# V2_aktuell_StdTeile.net
KiCad netlist of a schematic drawn in EAGLE
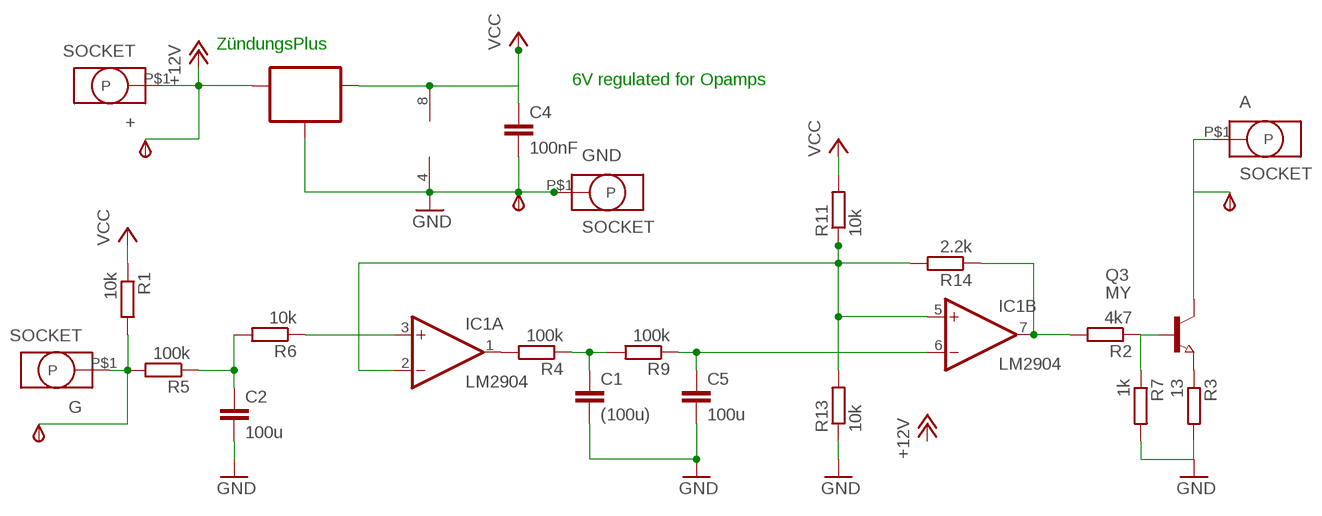
[diagram p0: schematic, sheet 1]

(export (version "E")
  (design (tool "Eeschema 10.0.6"))
  (components
    (comp (ref "+")
      (value "SOCKET")
      (footprint "eagle-import:ID2.5MM")
      (libsource (lib "eagle-import") (part "SOCKET"))
    )
    (comp (ref "A")
      (value "SOCKET")
      (footprint "eagle-import:ID2.5MM")
      (libsource (lib "eagle-import") (part "SOCKET"))
    )
    (comp (ref "C1")
      (value "(100u)")
      (footprint "eagle-import:C1206K")
      (libsource (lib "eagle-import") (part "C-EUC1206K"))
    )
    (comp (ref "C2")
      (value "100u")
      (footprint "eagle-import:C1206K")
      (libsource (lib "eagle-import") (part "C-EUC1206K"))
    )
    (comp (ref "C4")
      (value "100nF")
      (footprint "eagle-import:C0805")
      (libsource (lib "eagle-import") (part "C-EUC0805"))
    )
    (comp (ref "C5")
      (value "100u")
      (footprint "eagle-import:C1206K")
      (libsource (lib "eagle-import") (part "C-EUC1206K"))
    )
    (comp (ref "G")
      (value "SOCKET")
      (footprint "eagle-import:ID2.5MM")
      (libsource (lib "eagle-import") (part "SOCKET"))
    )
    (comp (ref "GND")
      (value "SOCKET")
      (footprint "eagle-import:ID2.5MM")
      (libsource (lib "eagle-import") (part "SOCKET"))
    )
    (comp (ref "GND_")
      (value "TPSB2.0")
      (footprint "eagle-import:B2.0")
      (libsource (lib "eagle-import") (part "TPSB2.0"))
    )
    (comp (ref "IC1")
      (value "LM2904")
      (footprint "eagle-import:SO08")
      (libsource (lib "eagle-import") (part "LM358D"))
    )
    (comp (ref "IC2")
      (value "70L06")
      (footprint "eagle-import:SOT89_ROUND")
      (libsource (lib "eagle-import") (part "78LXXSOT89_ROUND"))
    )
    (comp (ref "IN")
      (value "TPSB2.0")
      (footprint "eagle-import:B2.0")
      (libsource (lib "eagle-import") (part "TPSB2.0"))
    )
    (comp (ref "OUT")
      (value "TPSB2.0")
      (footprint "eagle-import:B2.0")
      (libsource (lib "eagle-import") (part "TPSB2.0"))
    )
    (comp (ref "Q3")
      (value "MY")
      (footprint "eagle-import:SOT89")
      (libsource (lib "eagle-import") (part "NPN-TRANSISTOR_SOT89"))
    )
    (comp (ref "R1")
      (value "10k")
      (footprint "eagle-import:R0805")
      (libsource (lib "eagle-import") (part "R-EU_R0805"))
    )
    (comp (ref "R2")
      (value "4k7")
      (footprint "eagle-import:R0805")
      (libsource (lib "eagle-import") (part "R-EU_R0805"))
    )
    (comp (ref "R3")
      (value "13")
      (footprint "eagle-import:R1206")
      (libsource (lib "eagle-import") (part "R-EU_R1206"))
    )
    (comp (ref "R4")
      (value "100k")
      (footprint "eagle-import:R0805")
      (libsource (lib "eagle-import") (part "R-EU_R0805"))
    )
    (comp (ref "R5")
      (value "100k")
      (footprint "eagle-import:R0805")
      (libsource (lib "eagle-import") (part "R-EU_R0805"))
    )
    (comp (ref "R6")
      (value "10k")
      (footprint "eagle-import:R0805")
      (libsource (lib "eagle-import") (part "R-EU_R0805"))
    )
    (comp (ref "R7")
      (value "1k")
      (footprint "eagle-import:R0805")
      (libsource (lib "eagle-import") (part "R-EU_R0805"))
    )
    (comp (ref "R9")
      (value "100k")
      (footprint "eagle-import:R0805")
      (libsource (lib "eagle-import") (part "R-EU_R0805"))
    )
    (comp (ref "R11")
      (value "10k")
      (footprint "eagle-import:R0805")
      (libsource (lib "eagle-import") (part "R-EU_R0805"))
    )
    (comp (ref "R13")
      (value "10k")
      (footprint "eagle-import:R0805")
      (libsource (lib "eagle-import") (part "R-EU_R0805"))
    )
    (comp (ref "R14")
      (value "2.2k")
      (footprint "eagle-import:R0805")
      (libsource (lib "eagle-import") (part "R-EU_R0805"))
    )
    (comp (ref "V+")
      (value "TPSB2.0")
      (footprint "eagle-import:B2.0")
      (libsource (lib "eagle-import") (part "TPSB2.0"))
    )
  )
  (nets
    (net (code "1") (name "+12V") (class "Default")
      (node (ref "+") (pin "P$1") (pinfunction "P_P$1") (pintype "bidirectional"))
      (node (ref "IC2") (pin "3") (pinfunction "IN_3") (pintype "input"))
      (node (ref "V+") (pin "TP") (pinfunction "PP_TP") (pintype "input"))
    )
    (net (code "2") (name "GND") (class "Default")
      (node (ref "C1") (pin "2") (pinfunction "2_2") (pintype "passive"))
      (node (ref "C2") (pin "2") (pinfunction "2_2") (pintype "passive"))
      (node (ref "C4") (pin "2") (pinfunction "2_2") (pintype "passive"))
      (node (ref "C5") (pin "2") (pinfunction "2_2") (pintype "passive"))
      (node (ref "GND") (pin "P$1") (pinfunction "P_P$1") (pintype "bidirectional"))
      (node (ref "GND_") (pin "TP") (pinfunction "PP_TP") (pintype "input"))
      (node (ref "IC1") (pin "4") (pinfunction "V-_4") (pintype "power_in"))
      (node (ref "IC2") (pin "2") (pinfunction "GND_2") (pintype "input"))
      (node (ref "IC2") (pin "2@1") (pinfunction "GND_2@1") (pintype "input"))
      (node (ref "R13") (pin "1") (pinfunction "1_1") (pintype "passive"))
      (node (ref "R3") (pin "2") (pinfunction "2_2") (pintype "passive"))
      (node (ref "R7") (pin "2") (pinfunction "2_2") (pintype "passive"))
    )
    (net (code "3") (name "Net-(A-P)") (class "Default")
      (node (ref "A") (pin "P$1") (pinfunction "P_P$1") (pintype "bidirectional"))
      (node (ref "OUT") (pin "TP") (pinfunction "PP_TP") (pintype "input"))
      (node (ref "Q3") (pin "2") (pinfunction "C_2") (pintype "passive"))
    )
    (net (code "4") (name "Net-(C1-Pad1)") (class "Default")
      (node (ref "C1") (pin "1") (pinfunction "1_1") (pintype "passive"))
      (node (ref "R4") (pin "1") (pinfunction "1_1") (pintype "passive"))
      (node (ref "R9") (pin "2") (pinfunction "2_2") (pintype "passive"))
    )
    (net (code "5") (name "Net-(C2-Pad1)") (class "Default")
      (node (ref "C2") (pin "1") (pinfunction "1_1") (pintype "passive"))
      (node (ref "R5") (pin "1") (pinfunction "1_1") (pintype "passive"))
      (node (ref "R6") (pin "2") (pinfunction "2_2") (pintype "passive"))
    )
    (net (code "6") (name "Net-(G-P)") (class "Default")
      (node (ref "G") (pin "P$1") (pinfunction "P_P$1") (pintype "bidirectional"))
      (node (ref "IN") (pin "TP") (pinfunction "PP_TP") (pintype "input"))
      (node (ref "R1") (pin "2") (pinfunction "2_2") (pintype "passive"))
      (node (ref "R5") (pin "2") (pinfunction "2_2") (pintype "passive"))
    )
    (net (code "7") (name "Net-(IC1A-+IN)") (class "Default")
      (node (ref "IC1") (pin "3") (pinfunction "+IN_3") (pintype "input"))
      (node (ref "R6") (pin "1") (pinfunction "1_1") (pintype "passive"))
    )
    (net (code "8") (name "Net-(IC1A--IN)") (class "Default")
      (node (ref "IC1") (pin "2") (pinfunction "-IN_2") (pintype "input"))
      (node (ref "IC1") (pin "5") (pinfunction "+IN_5") (pintype "input"))
      (node (ref "R11") (pin "1") (pinfunction "1_1") (pintype "passive"))
      (node (ref "R13") (pin "2") (pinfunction "2_2") (pintype "passive"))
      (node (ref "R14") (pin "2") (pinfunction "2_2") (pintype "passive"))
    )
    (net (code "9") (name "Net-(IC1A-OUT)") (class "Default")
      (node (ref "IC1") (pin "1") (pinfunction "OUT_1") (pintype "output"))
      (node (ref "R4") (pin "2") (pinfunction "2_2") (pintype "passive"))
    )
    (net (code "10") (name "Net-(IC1B--IN)") (class "Default")
      (node (ref "C5") (pin "1") (pinfunction "1_1") (pintype "passive"))
      (node (ref "IC1") (pin "6") (pinfunction "-IN_6") (pintype "input"))
      (node (ref "R9") (pin "1") (pinfunction "1_1") (pintype "passive"))
    )
    (net (code "11") (name "Net-(IC1B-OUT)") (class "Default")
      (node (ref "IC1") (pin "7") (pinfunction "OUT_7") (pintype "output"))
      (node (ref "R14") (pin "1") (pinfunction "1_1") (pintype "passive"))
      (node (ref "R2") (pin "2") (pinfunction "2_2") (pintype "passive"))
    )
    (net (code "12") (name "Net-(Q3-B)") (class "Default")
      (node (ref "Q3") (pin "1") (pinfunction "B_1") (pintype "passive"))
      (node (ref "R2") (pin "1") (pinfunction "1_1") (pintype "passive"))
      (node (ref "R7") (pin "1") (pinfunction "1_1") (pintype "passive"))
    )
    (net (code "13") (name "Net-(Q3-E)") (class "Default")
      (node (ref "Q3") (pin "3") (pinfunction "E_3") (pintype "passive"))
      (node (ref "R3") (pin "1") (pinfunction "1_1") (pintype "passive"))
    )
    (net (code "14") (name "VCC") (class "Default")
      (node (ref "C4") (pin "1") (pinfunction "1_1") (pintype "passive"))
      (node (ref "IC1") (pin "8") (pinfunction "V+_8") (pintype "power_in"))
      (node (ref "IC2") (pin "1") (pinfunction "OUT_1") (pintype "passive"))
      (node (ref "R1") (pin "1") (pinfunction "1_1") (pintype "passive"))
      (node (ref "R11") (pin "2") (pinfunction "2_2") (pintype "passive"))
    )
  )
)
